# PiHat.net
KiCad netlist of a schematic drawn in EAGLE
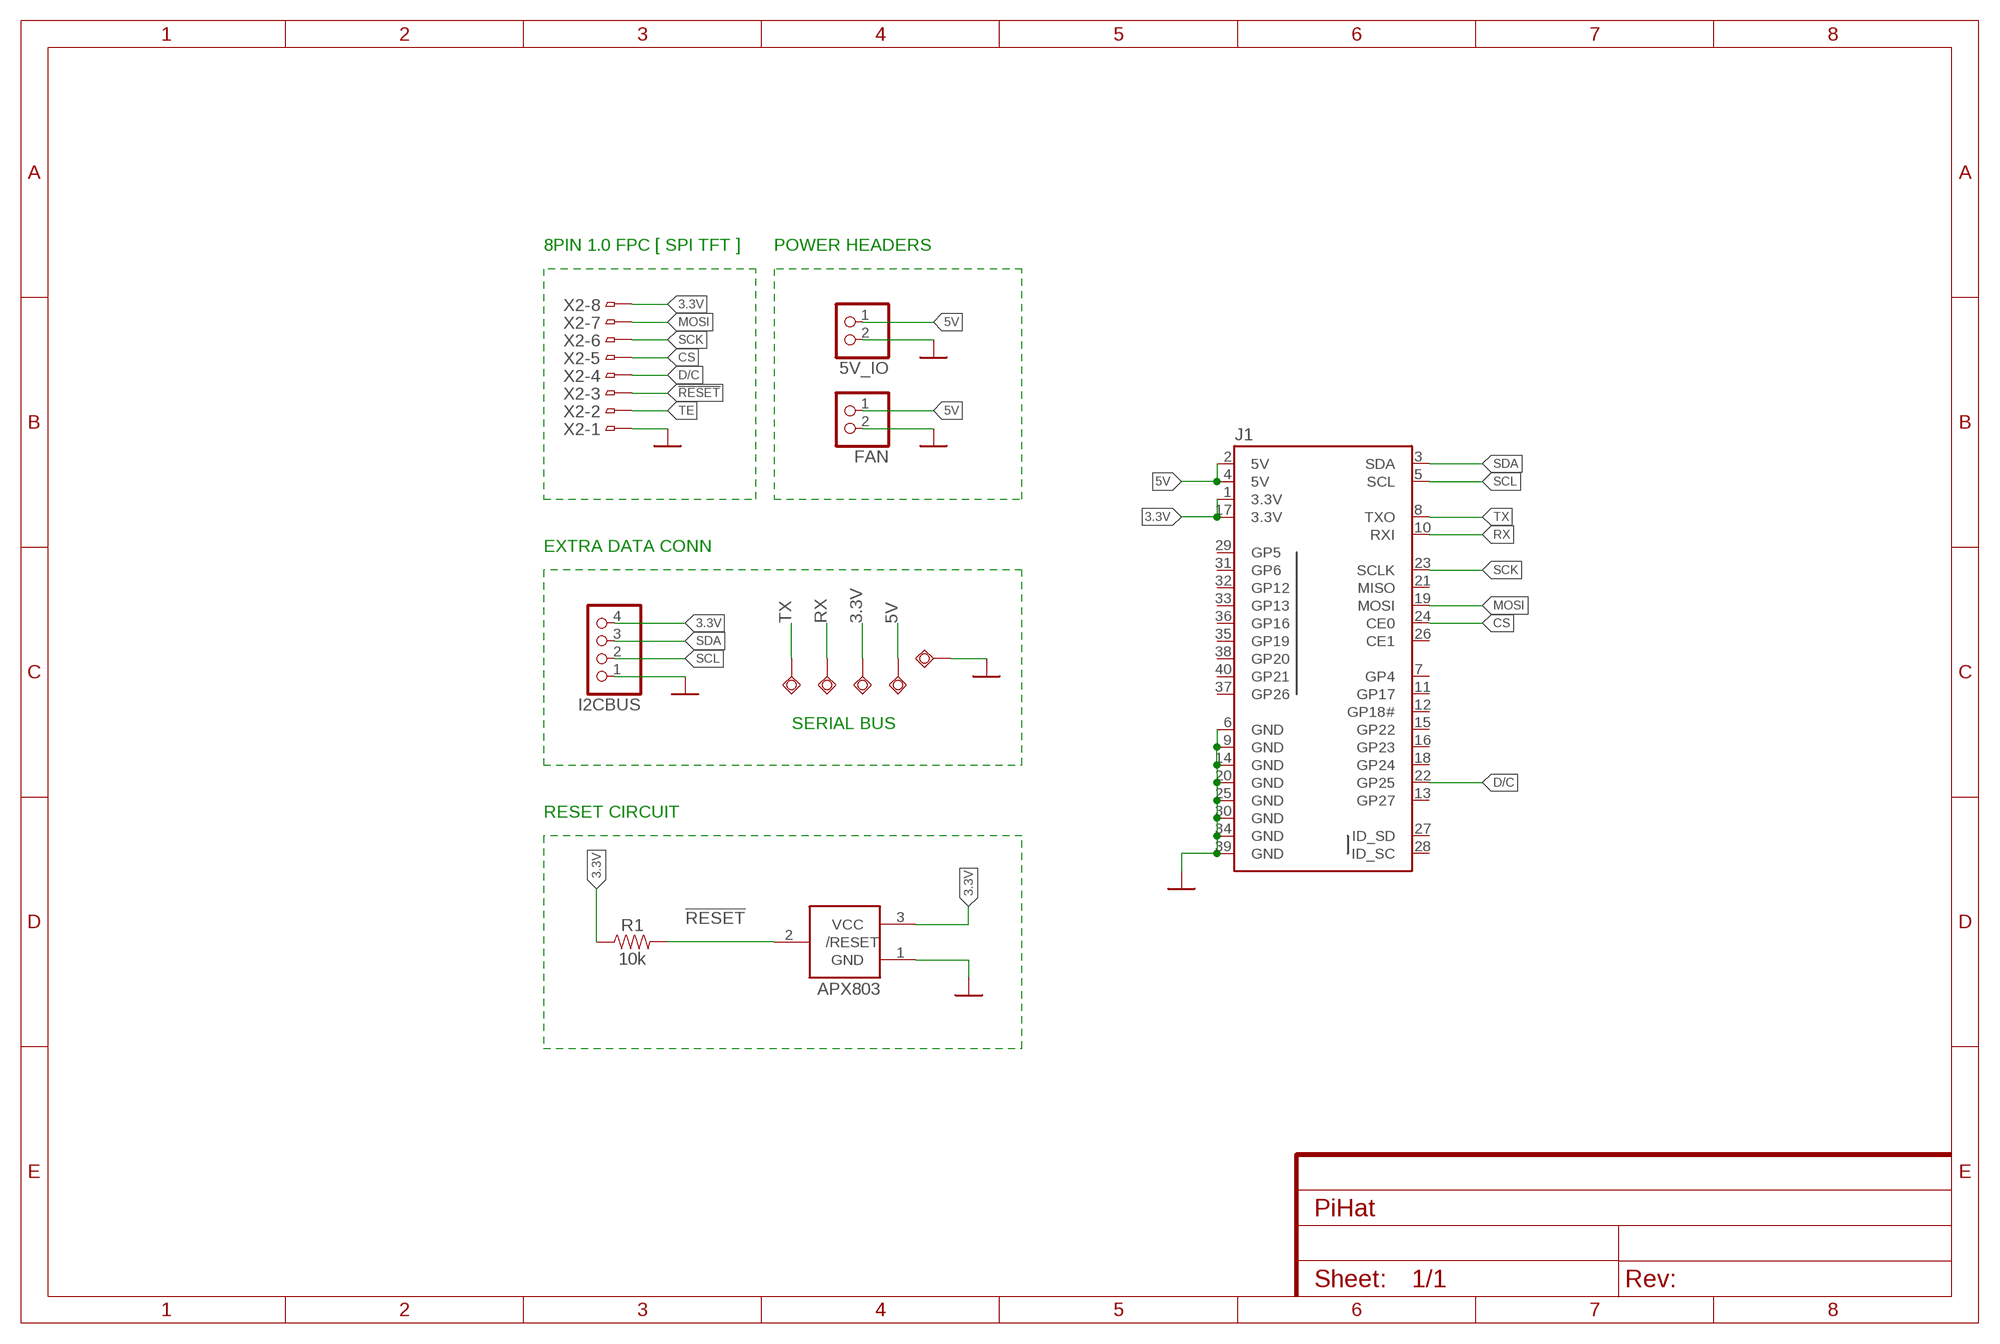
[diagram p0: schematic, sheet 1]

(export (version "E")
  (design (tool "Eeschema 10.0.6"))
  (components
    (comp (ref "5V_IO")
      (value "ONBOARDCONTROLINTERFACE_LED-BADGE_SCHEMATIC_ADAFRUIT_JST_2PIN-SMT-RA")
      (footprint "eagle-import:ONBOARDCONTROLINTERFACE_LED-BADGE_SCHEMATIC_ADAFRUIT_JST-PH-2-SMT-RA")
      (libsource (lib "eagle-import") (part "ONBOARDCONTROLINTERFACE_LED-BADGE_SCHEMATIC_ADAFRUIT_JST_2PIN-SMT-RA"))
    )
    (comp (ref "APX803")
      (value "ADAFRUIT_AXP083-SAG")
      (footprint "eagle-import:ADAFRUIT_SOT23")
      (libsource (lib "eagle-import") (part "ADAFRUIT_AXP083-SAG"))
    )
    (comp (ref "FAN")
      (value "ONBOARDCONTROLINTERFACE_LED-BADGE_SCHEMATIC_ADAFRUIT_JST_2PIN-SMT-RA")
      (footprint "eagle-import:ONBOARDCONTROLINTERFACE_LED-BADGE_SCHEMATIC_ADAFRUIT_JST-PH-2-SMT-RA")
      (libsource (lib "eagle-import") (part "ONBOARDCONTROLINTERFACE_LED-BADGE_SCHEMATIC_ADAFRUIT_JST_2PIN-SMT-RA"))
    )
    (comp (ref "I2CBUS")
      (value "MICROBUILDER_JST_4PIN")
      (footprint "eagle-import:MICROBUILDER_JSTPH4")
      (libsource (lib "eagle-import") (part "MICROBUILDER_JST_4PIN"))
    )
    (comp (ref "J1")
      (value "DESTINYSENSORFINAL_SPARKFUN-CONNECTORS_RASPBERRYPI-40-PIN-GPIO_PTH_NO_SHROUD")
      (footprint "eagle-import:DESTINYSENSORFINAL_SPARKFUN-CONNECTORS_2X20")
      (libsource (lib "eagle-import") (part "DESTINYSENSORFINAL_SPARKFUN-CONNECTORS_RASPBERRYPI-40-PIN-GPIO_PTH_NO_SHROUD"))
    )
    (comp (ref "R1")
      (value "10k")
      (footprint "eagle-import:ARDUINO_3V_TTL_INTERFACE_2_PI_SPARKFUN-RESISTORS_0603_1")
      (libsource (lib "eagle-import") (part "ARDUINO_3V_TTL_INTERFACE_2_PI_SPARKFUN-RESISTORS_10KOHM-0603-1/10W-1%"))
    )
    (comp (ref "TP1")
      (value "DESTINYSENSORFINAL_ARDUINO_3V_TTL_INTERFACE_2_PI_TESTPAD_TPSQTP20SQ")
      (footprint "eagle-import:DESTINYSENSORFINAL_ARDUINO_3V_TTL_INTERFACE_2_PI_TESTPAD_TP20SQ")
      (libsource (lib "eagle-import") (part "DESTINYSENSORFINAL_ARDUINO_3V_TTL_INTERFACE_2_PI_TESTPAD_TPSQTP20SQ"))
    )
    (comp (ref "TP2")
      (value "DESTINYSENSORFINAL_ARDUINO_3V_TTL_INTERFACE_2_PI_TESTPAD_TPSQTP20SQ")
      (footprint "eagle-import:DESTINYSENSORFINAL_ARDUINO_3V_TTL_INTERFACE_2_PI_TESTPAD_TP20SQ")
      (libsource (lib "eagle-import") (part "DESTINYSENSORFINAL_ARDUINO_3V_TTL_INTERFACE_2_PI_TESTPAD_TPSQTP20SQ"))
    )
    (comp (ref "TP3")
      (value "DESTINYSENSORFINAL_ARDUINO_3V_TTL_INTERFACE_2_PI_TESTPAD_TPSQTP20SQ")
      (footprint "eagle-import:DESTINYSENSORFINAL_ARDUINO_3V_TTL_INTERFACE_2_PI_TESTPAD_TP20SQ")
      (libsource (lib "eagle-import") (part "DESTINYSENSORFINAL_ARDUINO_3V_TTL_INTERFACE_2_PI_TESTPAD_TPSQTP20SQ"))
    )
    (comp (ref "TP4")
      (value "DESTINYSENSORFINAL_ARDUINO_3V_TTL_INTERFACE_2_PI_TESTPAD_TPSQTP20SQ")
      (footprint "eagle-import:DESTINYSENSORFINAL_ARDUINO_3V_TTL_INTERFACE_2_PI_TESTPAD_TP20SQ")
      (libsource (lib "eagle-import") (part "DESTINYSENSORFINAL_ARDUINO_3V_TTL_INTERFACE_2_PI_TESTPAD_TPSQTP20SQ"))
    )
    (comp (ref "TP5")
      (value "DESTINYSENSORFINAL_ARDUINO_3V_TTL_INTERFACE_2_PI_TESTPAD_TPSQTP20SQ")
      (footprint "eagle-import:DESTINYSENSORFINAL_ARDUINO_3V_TTL_INTERFACE_2_PI_TESTPAD_TP20SQ")
      (libsource (lib "eagle-import") (part "DESTINYSENSORFINAL_ARDUINO_3V_TTL_INTERFACE_2_PI_TESTPAD_TPSQTP20SQ"))
    )
    (comp (ref "X2")
      (value "SCREENBREAKOUT_SCREENBREAKOUT_LEDMATRIXFPCCONNECTOR_CON-HIROSE_FH12-08S-1SH")
      (footprint "eagle-import:SCREENBREAKOUT_SCREENBREAKOUT_LEDMATRIXFPCCONNECTOR_CON-HIROSE_FH12-08S-1SH")
      (libsource (lib "eagle-import") (part "SCREENBREAKOUT_SCREENBREAKOUT_LEDMATRIXFPCCONNECTOR_CON-HIROSE_FH12-08S-1SH"))
    )
  )
  (nets
    (net (code "1") (name "/~{RESET}") (class "Default")
      (node (ref "APX803") (pin "2") (pinfunction "/RESET_2") (pintype "output"))
      (node (ref "R1") (pin "2") (pinfunction "2_2") (pintype "passive"))
      (node (ref "X2") (pin "3") (pinfunction "1_3") (pintype "passive"))
    )
    (net (code "2") (name "3-5-PIN-SMD_GND") (class "Default")
      (node (ref "5V_IO") (pin "2") (pinfunction "1_2") (pintype "passive"))
      (node (ref "APX803") (pin "1") (pinfunction "GND_1") (pintype "power_in"))
      (node (ref "FAN") (pin "2") (pinfunction "1_2") (pintype "passive"))
      (node (ref "I2CBUS") (pin "1") (pinfunction "1_1") (pintype "passive"))
      (node (ref "J1") (pin "14") (pinfunction "GND_14") (pintype "power_in"))
      (node (ref "J1") (pin "20") (pinfunction "GND_20") (pintype "power_in"))
      (node (ref "J1") (pin "25") (pinfunction "GND_25") (pintype "power_in"))
      (node (ref "J1") (pin "30") (pinfunction "GND_30") (pintype "power_in"))
      (node (ref "J1") (pin "34") (pinfunction "GND_34") (pintype "power_in"))
      (node (ref "J1") (pin "39") (pinfunction "GND_39") (pintype "power_in"))
      (node (ref "J1") (pin "6") (pinfunction "GND_6") (pintype "power_in"))
      (node (ref "J1") (pin "9") (pinfunction "GND_9") (pintype "power_in"))
      (node (ref "TP5") (pin "TP") (pinfunction "TP_TP") (pintype "input"))
      (node (ref "X2") (pin "1") (pinfunction "1_1") (pintype "passive"))
    )
    (net (code "3") (name "3.3V") (class "Default")
      (node (ref "APX803") (pin "3") (pinfunction "VCC_3") (pintype "power_in"))
      (node (ref "I2CBUS") (pin "4") (pinfunction "4_4") (pintype "passive"))
      (node (ref "J1") (pin "1") (pinfunction "3.3V_1") (pintype "power_in"))
      (node (ref "J1") (pin "17") (pinfunction "3.3V_17") (pintype "power_in"))
      (node (ref "R1") (pin "1") (pinfunction "1_1") (pintype "passive"))
      (node (ref "TP3") (pin "TP") (pinfunction "TP_TP") (pintype "input"))
      (node (ref "X2") (pin "8") (pinfunction "1_8") (pintype "passive"))
    )
    (net (code "4") (name "5V") (class "Default")
      (node (ref "5V_IO") (pin "1") (pinfunction "2_1") (pintype "passive"))
      (node (ref "FAN") (pin "1") (pinfunction "2_1") (pintype "passive"))
      (node (ref "J1") (pin "2") (pinfunction "5V_2") (pintype "power_in"))
      (node (ref "J1") (pin "4") (pinfunction "5V_4") (pintype "power_in"))
      (node (ref "TP4") (pin "TP") (pinfunction "TP_TP") (pintype "input"))
    )
    (net (code "5") (name "CS") (class "Default")
      (node (ref "J1") (pin "24") (pinfunction "CE0_24") (pintype "output"))
      (node (ref "X2") (pin "5") (pinfunction "1_5") (pintype "passive"))
    )
    (net (code "6") (name "D{slash}C") (class "Default")
      (node (ref "J1") (pin "22") (pinfunction "GP25_22") (pintype "bidirectional"))
      (node (ref "X2") (pin "4") (pinfunction "1_4") (pintype "passive"))
    )
    (net (code "7") (name "MOSI") (class "Default")
      (node (ref "J1") (pin "19") (pinfunction "MOSI_19") (pintype "output"))
      (node (ref "X2") (pin "7") (pinfunction "1_7") (pintype "passive"))
    )
    (net (code "8") (name "RX") (class "Default")
      (node (ref "J1") (pin "10") (pinfunction "RXI_10") (pintype "input"))
      (node (ref "TP2") (pin "TP") (pinfunction "TP_TP") (pintype "input"))
    )
    (net (code "9") (name "SCK") (class "Default")
      (node (ref "J1") (pin "23") (pinfunction "SCLK_23") (pintype "output"))
      (node (ref "X2") (pin "6") (pinfunction "1_6") (pintype "passive"))
    )
    (net (code "10") (name "SCL") (class "Default")
      (node (ref "I2CBUS") (pin "2") (pinfunction "2_2") (pintype "passive"))
      (node (ref "J1") (pin "5") (pinfunction "SCL_5") (pintype "bidirectional"))
    )
    (net (code "11") (name "SDA") (class "Default")
      (node (ref "I2CBUS") (pin "3") (pinfunction "3_3") (pintype "passive"))
      (node (ref "J1") (pin "3") (pinfunction "SDA_3") (pintype "bidirectional"))
    )
    (net (code "12") (name "TE") (class "Default")
      (node (ref "X2") (pin "2") (pinfunction "1_2") (pintype "passive"))
    )
    (net (code "13") (name "TX") (class "Default")
      (node (ref "J1") (pin "8") (pinfunction "TXO_8") (pintype "output"))
      (node (ref "TP1") (pin "TP") (pinfunction "TP_TP") (pintype "input"))
    )
    (net (code "14") (name "unconnected-(J1-CE1-Pad26)") (class "Default")
      (node (ref "J1") (pin "26") (pinfunction "CE1_26") (pintype "output"))
    )
    (net (code "15") (name "unconnected-(J1-GP4-Pad7)") (class "Default")
      (node (ref "J1") (pin "7") (pinfunction "GP4_7") (pintype "bidirectional"))
    )
    (net (code "16") (name "unconnected-(J1-GP5-Pad29)") (class "Default")
      (node (ref "J1") (pin "29") (pinfunction "GP5_29") (pintype "bidirectional"))
    )
    (net (code "17") (name "unconnected-(J1-GP6-Pad31)") (class "Default")
      (node (ref "J1") (pin "31") (pinfunction "GP6_31") (pintype "bidirectional"))
    )
    (net (code "18") (name "unconnected-(J1-GP12-Pad32)") (class "Default")
      (node (ref "J1") (pin "32") (pinfunction "GP12_32") (pintype "bidirectional"))
    )
    (net (code "19") (name "unconnected-(J1-GP13-Pad33)") (class "Default")
      (node (ref "J1") (pin "33") (pinfunction "GP13_33") (pintype "bidirectional"))
    )
    (net (code "20") (name "unconnected-(J1-GP16-Pad36)") (class "Default")
      (node (ref "J1") (pin "36") (pinfunction "GP16_36") (pintype "bidirectional"))
    )
    (net (code "21") (name "unconnected-(J1-GP17-Pad11)") (class "Default")
      (node (ref "J1") (pin "11") (pinfunction "GP17_11") (pintype "bidirectional"))
    )
    (net (code "22") (name "unconnected-(J1-GP18#-Pad12)") (class "Default")
      (node (ref "J1") (pin "12") (pinfunction "GP18#_12") (pintype "bidirectional"))
    )
    (net (code "23") (name "unconnected-(J1-GP19-Pad35)") (class "Default")
      (node (ref "J1") (pin "35") (pinfunction "GP19_35") (pintype "bidirectional"))
    )
    (net (code "24") (name "unconnected-(J1-GP20-Pad38)") (class "Default")
      (node (ref "J1") (pin "38") (pinfunction "GP20_38") (pintype "bidirectional"))
    )
    (net (code "25") (name "unconnected-(J1-GP21-Pad40)") (class "Default")
      (node (ref "J1") (pin "40") (pinfunction "GP21_40") (pintype "bidirectional"))
    )
    (net (code "26") (name "unconnected-(J1-GP22-Pad15)") (class "Default")
      (node (ref "J1") (pin "15") (pinfunction "GP22_15") (pintype "bidirectional"))
    )
    (net (code "27") (name "unconnected-(J1-GP23-Pad16)") (class "Default")
      (node (ref "J1") (pin "16") (pinfunction "GP23_16") (pintype "bidirectional"))
    )
    (net (code "28") (name "unconnected-(J1-GP24-Pad18)") (class "Default")
      (node (ref "J1") (pin "18") (pinfunction "GP24_18") (pintype "bidirectional"))
    )
    (net (code "29") (name "unconnected-(J1-GP26-Pad37)") (class "Default")
      (node (ref "J1") (pin "37") (pinfunction "GP26_37") (pintype "bidirectional"))
    )
    (net (code "30") (name "unconnected-(J1-GP27-Pad13)") (class "Default")
      (node (ref "J1") (pin "13") (pinfunction "GP27_13") (pintype "bidirectional"))
    )
    (net (code "31") (name "unconnected-(J1-ID_SC-Pad28)") (class "Default")
      (node (ref "J1") (pin "28") (pinfunction "ID_SC_28") (pintype "bidirectional"))
    )
    (net (code "32") (name "unconnected-(J1-ID_SD-Pad27)") (class "Default")
      (node (ref "J1") (pin "27") (pinfunction "ID_SD_27") (pintype "bidirectional"))
    )
    (net (code "33") (name "unconnected-(J1-MISO-Pad21)") (class "Default")
      (node (ref "J1") (pin "21") (pinfunction "MISO_21") (pintype "input"))
    )
  )
)
